# BSU_RTD.net
KiCad netlist of a schematic drawn in Altium Designer
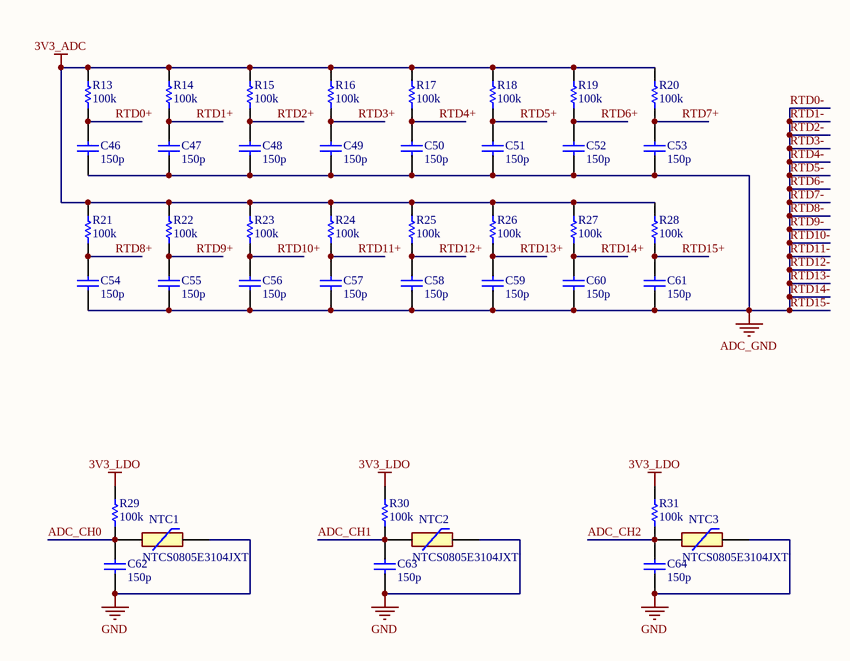
[diagram p0: BSU_RTD.SchDoc]

(export (version "E")
  (design (tool "Eeschema 10.0.6"))
  (components
    (comp (ref "C46")
      (value "150p")
      (footprint "0603_SMD_C")
      (description "0603 SMD Capacitor")
      (libsource (lib "BMS_ShareComponentLibrary") (part "0603_SMD_Capacitor"))
    )
    (comp (ref "C47")
      (value "150p")
      (footprint "0603_SMD_C")
      (description "0603 SMD Capacitor")
      (libsource (lib "BMS_ShareComponentLibrary") (part "0603_SMD_Capacitor"))
    )
    (comp (ref "C48")
      (value "150p")
      (footprint "0603_SMD_C")
      (description "0603 SMD Capacitor")
      (libsource (lib "BMS_ShareComponentLibrary") (part "0603_SMD_Capacitor"))
    )
    (comp (ref "C49")
      (value "150p")
      (footprint "0603_SMD_C")
      (description "0603 SMD Capacitor")
      (libsource (lib "BMS_ShareComponentLibrary") (part "0603_SMD_Capacitor"))
    )
    (comp (ref "C50")
      (value "150p")
      (footprint "0603_SMD_C")
      (description "0603 SMD Capacitor")
      (libsource (lib "BMS_ShareComponentLibrary") (part "0603_SMD_Capacitor"))
    )
    (comp (ref "C51")
      (value "150p")
      (footprint "0603_SMD_C")
      (description "0603 SMD Capacitor")
      (libsource (lib "BMS_ShareComponentLibrary") (part "0603_SMD_Capacitor"))
    )
    (comp (ref "C52")
      (value "150p")
      (footprint "0603_SMD_C")
      (description "0603 SMD Capacitor")
      (libsource (lib "BMS_ShareComponentLibrary") (part "0603_SMD_Capacitor"))
    )
    (comp (ref "C53")
      (value "150p")
      (footprint "0603_SMD_C")
      (description "0603 SMD Capacitor")
      (libsource (lib "BMS_ShareComponentLibrary") (part "0603_SMD_Capacitor"))
    )
    (comp (ref "C54")
      (value "150p")
      (footprint "0603_SMD_C")
      (description "0603 SMD Capacitor")
      (libsource (lib "BMS_ShareComponentLibrary") (part "0603_SMD_Capacitor"))
    )
    (comp (ref "C55")
      (value "150p")
      (footprint "0603_SMD_C")
      (description "0603 SMD Capacitor")
      (libsource (lib "BMS_ShareComponentLibrary") (part "0603_SMD_Capacitor"))
    )
    (comp (ref "C56")
      (value "150p")
      (footprint "0603_SMD_C")
      (description "0603 SMD Capacitor")
      (libsource (lib "BMS_ShareComponentLibrary") (part "0603_SMD_Capacitor"))
    )
    (comp (ref "C57")
      (value "150p")
      (footprint "0603_SMD_C")
      (description "0603 SMD Capacitor")
      (libsource (lib "BMS_ShareComponentLibrary") (part "0603_SMD_Capacitor"))
    )
    (comp (ref "C58")
      (value "150p")
      (footprint "0603_SMD_C")
      (description "0603 SMD Capacitor")
      (libsource (lib "BMS_ShareComponentLibrary") (part "0603_SMD_Capacitor"))
    )
    (comp (ref "C59")
      (value "150p")
      (footprint "0603_SMD_C")
      (description "0603 SMD Capacitor")
      (libsource (lib "BMS_ShareComponentLibrary") (part "0603_SMD_Capacitor"))
    )
    (comp (ref "C60")
      (value "150p")
      (footprint "0603_SMD_C")
      (description "0603 SMD Capacitor")
      (libsource (lib "BMS_ShareComponentLibrary") (part "0603_SMD_Capacitor"))
    )
    (comp (ref "C61")
      (value "150p")
      (footprint "0603_SMD_C")
      (description "0603 SMD Capacitor")
      (libsource (lib "BMS_ShareComponentLibrary") (part "0603_SMD_Capacitor"))
    )
    (comp (ref "C62")
      (value "150p")
      (footprint "0805_SMD_C")
      (description "0805 SMD Capacitor")
      (libsource (lib "BMS_ShareComponentLibrary") (part "0805_SMD_Capacitor"))
    )
    (comp (ref "C63")
      (value "150p")
      (footprint "0805_SMD_C")
      (description "0805 SMD Capacitor")
      (libsource (lib "BMS_ShareComponentLibrary") (part "0805_SMD_Capacitor"))
    )
    (comp (ref "C64")
      (value "150p")
      (footprint "0805_SMD_C")
      (description "0805 SMD Capacitor")
      (libsource (lib "BMS_ShareComponentLibrary") (part "0805_SMD_Capacitor"))
    )
    (comp (ref "NTC1")
      (value "NTCS0805E3104JXT")
      (footprint "0805_SMD_R")
      (description "NTC Thermistors 100Kohms 5% SMD")
      (fields (field (name "MOUSER PART NUMBER") "594-NTCS0805E3104JXT"))
      (libsource (lib "BMS_ShareComponentLibrary") (part "0805_SMD_NTC_Thermistor_100k"))
    )
    (comp (ref "NTC2")
      (value "NTCS0805E3104JXT")
      (footprint "0805_SMD_R")
      (description "NTC Thermistors 100Kohms 5% SMD")
      (fields (field (name "MOUSER PART NUMBER") "594-NTCS0805E3104JXT"))
      (libsource (lib "BMS_ShareComponentLibrary") (part "0805_SMD_NTC_Thermistor_100k"))
    )
    (comp (ref "NTC3")
      (value "NTCS0805E3104JXT")
      (footprint "0805_SMD_R")
      (description "NTC Thermistors 100Kohms 5% SMD")
      (fields (field (name "MOUSER PART NUMBER") "594-NTCS0805E3104JXT"))
      (libsource (lib "BMS_ShareComponentLibrary") (part "0805_SMD_NTC_Thermistor_100k"))
    )
    (comp (ref "R13")
      (value "100k")
      (footprint "0603_SMD_R")
      (description "0603 SMD Resistor")
      (libsource (lib "BMS_ShareComponentLibrary") (part "0603_SMD_Resistor"))
    )
    (comp (ref "R14")
      (value "100k")
      (footprint "0603_SMD_R")
      (description "0603 SMD Resistor")
      (libsource (lib "BMS_ShareComponentLibrary") (part "0603_SMD_Resistor"))
    )
    (comp (ref "R15")
      (value "100k")
      (footprint "0603_SMD_R")
      (description "0603 SMD Resistor")
      (libsource (lib "BMS_ShareComponentLibrary") (part "0603_SMD_Resistor"))
    )
    (comp (ref "R16")
      (value "100k")
      (footprint "0603_SMD_R")
      (description "0603 SMD Resistor")
      (libsource (lib "BMS_ShareComponentLibrary") (part "0603_SMD_Resistor"))
    )
    (comp (ref "R17")
      (value "100k")
      (footprint "0603_SMD_R")
      (description "0603 SMD Resistor")
      (libsource (lib "BMS_ShareComponentLibrary") (part "0603_SMD_Resistor"))
    )
    (comp (ref "R18")
      (value "100k")
      (footprint "0603_SMD_R")
      (description "0603 SMD Resistor")
      (libsource (lib "BMS_ShareComponentLibrary") (part "0603_SMD_Resistor"))
    )
    (comp (ref "R19")
      (value "100k")
      (footprint "0603_SMD_R")
      (description "0603 SMD Resistor")
      (libsource (lib "BMS_ShareComponentLibrary") (part "0603_SMD_Resistor"))
    )
    (comp (ref "R20")
      (value "100k")
      (footprint "0603_SMD_R")
      (description "0603 SMD Resistor")
      (libsource (lib "BMS_ShareComponentLibrary") (part "0603_SMD_Resistor"))
    )
    (comp (ref "R21")
      (value "100k")
      (footprint "0603_SMD_R")
      (description "0603 SMD Resistor")
      (libsource (lib "BMS_ShareComponentLibrary") (part "0603_SMD_Resistor"))
    )
    (comp (ref "R22")
      (value "100k")
      (footprint "0603_SMD_R")
      (description "0603 SMD Resistor")
      (libsource (lib "BMS_ShareComponentLibrary") (part "0603_SMD_Resistor"))
    )
    (comp (ref "R23")
      (value "100k")
      (footprint "0603_SMD_R")
      (description "0603 SMD Resistor")
      (libsource (lib "BMS_ShareComponentLibrary") (part "0603_SMD_Resistor"))
    )
    (comp (ref "R24")
      (value "100k")
      (footprint "0603_SMD_R")
      (description "0603 SMD Resistor")
      (libsource (lib "BMS_ShareComponentLibrary") (part "0603_SMD_Resistor"))
    )
    (comp (ref "R25")
      (value "100k")
      (footprint "0603_SMD_R")
      (description "0603 SMD Resistor")
      (libsource (lib "BMS_ShareComponentLibrary") (part "0603_SMD_Resistor"))
    )
    (comp (ref "R26")
      (value "100k")
      (footprint "0603_SMD_R")
      (description "0603 SMD Resistor")
      (libsource (lib "BMS_ShareComponentLibrary") (part "0603_SMD_Resistor"))
    )
    (comp (ref "R27")
      (value "100k")
      (footprint "0603_SMD_R")
      (description "0603 SMD Resistor")
      (libsource (lib "BMS_ShareComponentLibrary") (part "0603_SMD_Resistor"))
    )
    (comp (ref "R28")
      (value "100k")
      (footprint "0603_SMD_R")
      (description "0603 SMD Resistor")
      (libsource (lib "BMS_ShareComponentLibrary") (part "0603_SMD_Resistor"))
    )
    (comp (ref "R29")
      (value "100k")
      (footprint "0805_SMD_R")
      (description "0805 SMD Resistor")
      (libsource (lib "BMS_ShareComponentLibrary") (part "0805_SMD_Resistor"))
    )
    (comp (ref "R30")
      (value "100k")
      (footprint "0805_SMD_R")
      (description "0805 SMD Resistor")
      (libsource (lib "BMS_ShareComponentLibrary") (part "0805_SMD_Resistor"))
    )
    (comp (ref "R31")
      (value "100k")
      (footprint "0805_SMD_R")
      (description "0805 SMD Resistor")
      (libsource (lib "BMS_ShareComponentLibrary") (part "0805_SMD_Resistor"))
    )
  )
  (nets
    (net (code "1") (name "/ADC_CH0") (class "Default")
      (node (ref "C62") (pin "2") (pinfunction "2_2") (pintype "passive"))
      (node (ref "NTC1") (pin "2") (pinfunction "2_2") (pintype "passive"))
      (node (ref "R29") (pin "1") (pinfunction "1_1") (pintype "passive"))
    )
    (net (code "2") (name "/ADC_CH1") (class "Default")
      (node (ref "C63") (pin "2") (pinfunction "2_2") (pintype "passive"))
      (node (ref "NTC2") (pin "2") (pinfunction "2_2") (pintype "passive"))
      (node (ref "R30") (pin "1") (pinfunction "1_1") (pintype "passive"))
    )
    (net (code "3") (name "/ADC_CH2") (class "Default")
      (node (ref "C64") (pin "2") (pinfunction "2_2") (pintype "passive"))
      (node (ref "NTC3") (pin "2") (pinfunction "2_2") (pintype "passive"))
      (node (ref "R31") (pin "1") (pinfunction "1_1") (pintype "passive"))
    )
    (net (code "4") (name "/RTD0+") (class "Default")
      (node (ref "C46") (pin "2") (pinfunction "2_2") (pintype "passive"))
      (node (ref "R13") (pin "1") (pinfunction "1_1") (pintype "passive"))
    )
    (net (code "5") (name "/RTD1+") (class "Default")
      (node (ref "C47") (pin "2") (pinfunction "2_2") (pintype "passive"))
      (node (ref "R14") (pin "1") (pinfunction "1_1") (pintype "passive"))
    )
    (net (code "6") (name "/RTD2+") (class "Default")
      (node (ref "C48") (pin "2") (pinfunction "2_2") (pintype "passive"))
      (node (ref "R15") (pin "1") (pinfunction "1_1") (pintype "passive"))
    )
    (net (code "7") (name "/RTD3+") (class "Default")
      (node (ref "C49") (pin "2") (pinfunction "2_2") (pintype "passive"))
      (node (ref "R16") (pin "1") (pinfunction "1_1") (pintype "passive"))
    )
    (net (code "8") (name "/RTD4+") (class "Default")
      (node (ref "C50") (pin "2") (pinfunction "2_2") (pintype "passive"))
      (node (ref "R17") (pin "1") (pinfunction "1_1") (pintype "passive"))
    )
    (net (code "9") (name "/RTD5+") (class "Default")
      (node (ref "C51") (pin "2") (pinfunction "2_2") (pintype "passive"))
      (node (ref "R18") (pin "1") (pinfunction "1_1") (pintype "passive"))
    )
    (net (code "10") (name "/RTD6+") (class "Default")
      (node (ref "C52") (pin "2") (pinfunction "2_2") (pintype "passive"))
      (node (ref "R19") (pin "1") (pinfunction "1_1") (pintype "passive"))
    )
    (net (code "11") (name "/RTD7+") (class "Default")
      (node (ref "C53") (pin "2") (pinfunction "2_2") (pintype "passive"))
      (node (ref "R20") (pin "1") (pinfunction "1_1") (pintype "passive"))
    )
    (net (code "12") (name "/RTD8+") (class "Default")
      (node (ref "C54") (pin "2") (pinfunction "2_2") (pintype "passive"))
      (node (ref "R21") (pin "1") (pinfunction "1_1") (pintype "passive"))
    )
    (net (code "13") (name "/RTD9+") (class "Default")
      (node (ref "C55") (pin "2") (pinfunction "2_2") (pintype "passive"))
      (node (ref "R22") (pin "1") (pinfunction "1_1") (pintype "passive"))
    )
    (net (code "14") (name "/RTD10+") (class "Default")
      (node (ref "C56") (pin "2") (pinfunction "2_2") (pintype "passive"))
      (node (ref "R23") (pin "1") (pinfunction "1_1") (pintype "passive"))
    )
    (net (code "15") (name "/RTD11+") (class "Default")
      (node (ref "C57") (pin "2") (pinfunction "2_2") (pintype "passive"))
      (node (ref "R24") (pin "1") (pinfunction "1_1") (pintype "passive"))
    )
    (net (code "16") (name "/RTD12+") (class "Default")
      (node (ref "C58") (pin "2") (pinfunction "2_2") (pintype "passive"))
      (node (ref "R25") (pin "1") (pinfunction "1_1") (pintype "passive"))
    )
    (net (code "17") (name "/RTD13+") (class "Default")
      (node (ref "C59") (pin "2") (pinfunction "2_2") (pintype "passive"))
      (node (ref "R26") (pin "1") (pinfunction "1_1") (pintype "passive"))
    )
    (net (code "18") (name "/RTD14+") (class "Default")
      (node (ref "C60") (pin "2") (pinfunction "2_2") (pintype "passive"))
      (node (ref "R27") (pin "1") (pinfunction "1_1") (pintype "passive"))
    )
    (net (code "19") (name "/RTD15+") (class "Default")
      (node (ref "C61") (pin "2") (pinfunction "2_2") (pintype "passive"))
      (node (ref "R28") (pin "1") (pinfunction "1_1") (pintype "passive"))
    )
    (net (code "20") (name "3V3_ADC") (class "Default")
      (node (ref "R13") (pin "2") (pinfunction "2_2") (pintype "passive"))
      (node (ref "R14") (pin "2") (pinfunction "2_2") (pintype "passive"))
      (node (ref "R15") (pin "2") (pinfunction "2_2") (pintype "passive"))
      (node (ref "R16") (pin "2") (pinfunction "2_2") (pintype "passive"))
      (node (ref "R17") (pin "2") (pinfunction "2_2") (pintype "passive"))
      (node (ref "R18") (pin "2") (pinfunction "2_2") (pintype "passive"))
      (node (ref "R19") (pin "2") (pinfunction "2_2") (pintype "passive"))
      (node (ref "R20") (pin "2") (pinfunction "2_2") (pintype "passive"))
      (node (ref "R21") (pin "2") (pinfunction "2_2") (pintype "passive"))
      (node (ref "R22") (pin "2") (pinfunction "2_2") (pintype "passive"))
      (node (ref "R23") (pin "2") (pinfunction "2_2") (pintype "passive"))
      (node (ref "R24") (pin "2") (pinfunction "2_2") (pintype "passive"))
      (node (ref "R25") (pin "2") (pinfunction "2_2") (pintype "passive"))
      (node (ref "R26") (pin "2") (pinfunction "2_2") (pintype "passive"))
      (node (ref "R27") (pin "2") (pinfunction "2_2") (pintype "passive"))
      (node (ref "R28") (pin "2") (pinfunction "2_2") (pintype "passive"))
    )
    (net (code "21") (name "3V3_LDO") (class "Default")
      (node (ref "R29") (pin "2") (pinfunction "2_2") (pintype "passive"))
      (node (ref "R30") (pin "2") (pinfunction "2_2") (pintype "passive"))
      (node (ref "R31") (pin "2") (pinfunction "2_2") (pintype "passive"))
    )
    (net (code "22") (name "ADC_GND") (class "Default")
      (node (ref "C46") (pin "1") (pinfunction "1_1") (pintype "passive"))
      (node (ref "C47") (pin "1") (pinfunction "1_1") (pintype "passive"))
      (node (ref "C48") (pin "1") (pinfunction "1_1") (pintype "passive"))
      (node (ref "C49") (pin "1") (pinfunction "1_1") (pintype "passive"))
      (node (ref "C50") (pin "1") (pinfunction "1_1") (pintype "passive"))
      (node (ref "C51") (pin "1") (pinfunction "1_1") (pintype "passive"))
      (node (ref "C52") (pin "1") (pinfunction "1_1") (pintype "passive"))
      (node (ref "C53") (pin "1") (pinfunction "1_1") (pintype "passive"))
      (node (ref "C54") (pin "1") (pinfunction "1_1") (pintype "passive"))
      (node (ref "C55") (pin "1") (pinfunction "1_1") (pintype "passive"))
      (node (ref "C56") (pin "1") (pinfunction "1_1") (pintype "passive"))
      (node (ref "C57") (pin "1") (pinfunction "1_1") (pintype "passive"))
      (node (ref "C58") (pin "1") (pinfunction "1_1") (pintype "passive"))
      (node (ref "C59") (pin "1") (pinfunction "1_1") (pintype "passive"))
      (node (ref "C60") (pin "1") (pinfunction "1_1") (pintype "passive"))
      (node (ref "C61") (pin "1") (pinfunction "1_1") (pintype "passive"))
    )
    (net (code "23") (name "GND") (class "Default")
      (node (ref "C62") (pin "1") (pinfunction "1_1") (pintype "passive"))
      (node (ref "C63") (pin "1") (pinfunction "1_1") (pintype "passive"))
      (node (ref "C64") (pin "1") (pinfunction "1_1") (pintype "passive"))
      (node (ref "NTC1") (pin "1") (pinfunction "1_1") (pintype "passive"))
      (node (ref "NTC2") (pin "1") (pinfunction "1_1") (pintype "passive"))
      (node (ref "NTC3") (pin "1") (pinfunction "1_1") (pintype "passive"))
    )
  )
)
